# adc-digital.net
KiCad netlist of a schematic drawn in Altium Designer
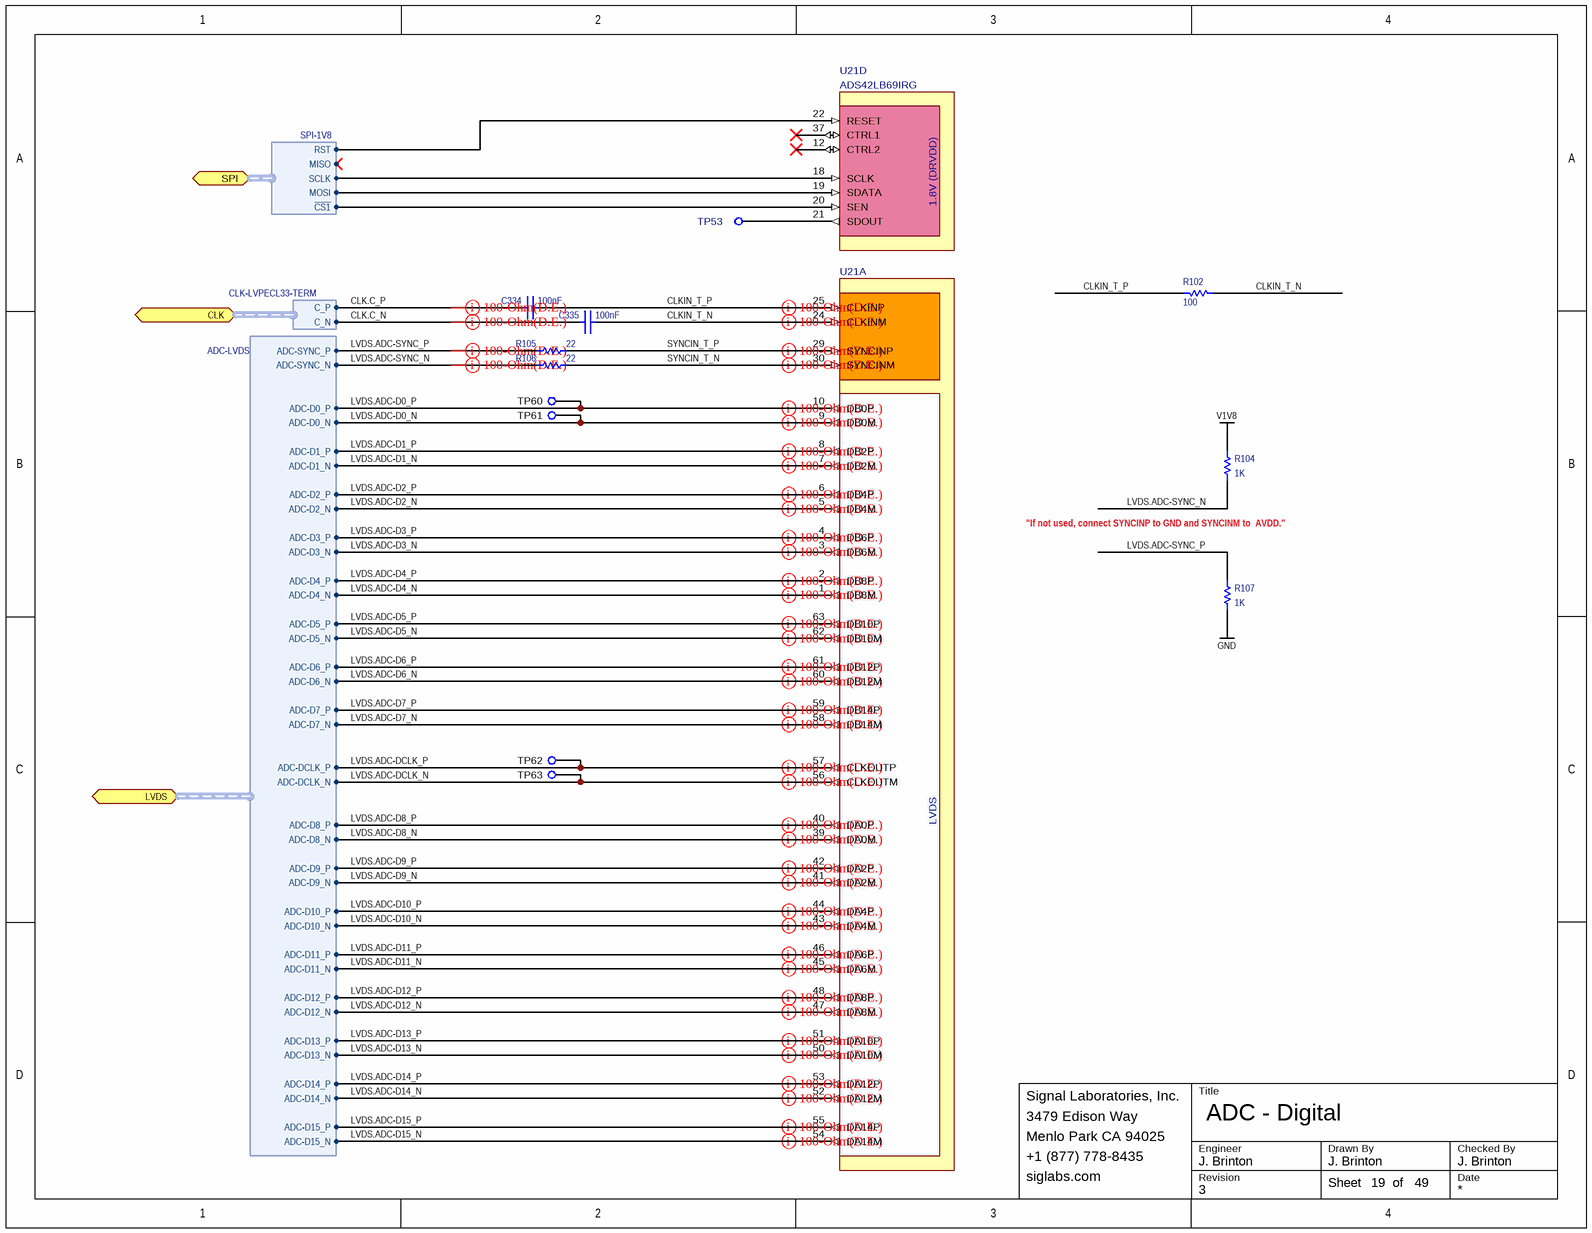
[diagram p0: adc-digital.SchDoc]

(export (version "E")
  (design (tool "Eeschema 10.0.6"))
  (components
    (comp (ref "C334")
      (value "100nF")
      (footprint "CAPC100X50X55L25N")
      (description "Ceramic Capacitor 100nF ±10% 16V X7R 0402")
      (fields (field (name "VOLTAGE") "16V") (field (name "MANUFACTURER") "Murata"))
      (libsource (lib "Graviton") (part "CAP 0402"))
    )
    (comp (ref "C335")
      (value "100nF")
      (footprint "CAPC100X50X55L25N")
      (description "Ceramic Capacitor 100nF ±10% 16V X7R 0402")
      (fields (field (name "VOLTAGE") "16V") (field (name "MANUFACTURER") "Murata"))
      (libsource (lib "Graviton") (part "CAP 0402"))
    )
    (comp (ref "R102")
      (value "100")
      (footprint "RESC1005X40N")
      (description "Thin Film Resistor 100 ±0.1% 0402")
      (fields (field (name "MANUFACTURER") "Panasonic") (field (name "TOLERANCE") "±0.1%"))
      (libsource (lib "Graviton") (part "RES 0402"))
    )
    (comp (ref "R104")
      (value "1K")
      (footprint "RESC1005X40N")
      (description "Thick Film Resistor 1k ±1% 0402")
      (fields (field (name "MANUFACTURER") "Yageo") (field (name "TOLERANCE") "±1%"))
      (libsource (lib "Graviton") (part "RES 0402"))
    )
    (comp (ref "R105")
      (value "22")
      (footprint "RESC1005X40N")
      (description "Thick Film Resistor 22 ±1% 0402")
      (fields (field (name "MANUFACTURER") "Yageo") (field (name "TOLERANCE") "±1%"))
      (libsource (lib "Graviton") (part "RES 0402"))
    )
    (comp (ref "R106")
      (value "22")
      (footprint "RESC1005X40N")
      (description "Thick Film Resistor 22 ±1% 0402")
      (fields (field (name "MANUFACTURER") "Yageo") (field (name "TOLERANCE") "±1%"))
      (libsource (lib "Graviton") (part "RES 0402"))
    )
    (comp (ref "R107")
      (value "1K")
      (footprint "RESC1005X40N")
      (description "Thick Film Resistor 1k ±1% 0402")
      (fields (field (name "MANUFACTURER") "Yageo") (field (name "TOLERANCE") "±1%"))
      (libsource (lib "Graviton") (part "RES 0402"))
    )
    (comp (ref "TP53")
      (value "TEST_POINT_SMD_50")
      (footprint "generic:TEST_POINT_SMD_10")
      (description "Test Point SMD")
      (libsource (lib "generic") (part "TEST_POINT_SMD_50"))
    )
    (comp (ref "TP60")
      (value "TEST_POINT_SMD_50")
      (footprint "generic:TEST_POINT_SMD_10")
      (description "Test Point SMD")
      (libsource (lib "generic") (part "TEST_POINT_SMD_50"))
    )
    (comp (ref "TP61")
      (value "TEST_POINT_SMD_50")
      (footprint "generic:TEST_POINT_SMD_10")
      (description "Test Point SMD")
      (libsource (lib "generic") (part "TEST_POINT_SMD_50"))
    )
    (comp (ref "TP62")
      (value "TEST_POINT_SMD_50")
      (footprint "generic:TEST_POINT_SMD_10")
      (description "Test Point SMD")
      (libsource (lib "generic") (part "TEST_POINT_SMD_50"))
    )
    (comp (ref "TP63")
      (value "TEST_POINT_SMD_50")
      (footprint "generic:TEST_POINT_SMD_10")
      (description "Test Point SMD")
      (libsource (lib "generic") (part "TEST_POINT_SMD_50"))
    )
    (comp (ref "U21")
      (value "ADS42LB69IRG")
      (footprint "S-PVQFN-N64")
      (description "Dual-Channel, 16-Bit, 250-MSPS Analog-to-Digital Converter")
      (fields (field (name "MANUFACTURER") "Texas Instruments"))
      (libsource (lib "ti") (part "ADS42LB69IRG"))
    )
  )
  (nets
    (net (code "4") (name "/CLK.C_N") (class "Default")
      (node (ref "C335") (pin "1") (pinfunction "1_1") (pintype "passive"))
    )
    (net (code "5") (name "/CLK.C_P") (class "Default")
      (node (ref "C334") (pin "1") (pinfunction "1_1") (pintype "passive"))
    )
    (net (code "6") (name "/CLKIN_T_N") (class "Default")
      (node (ref "C335") (pin "2") (pinfunction "2_2") (pintype "passive"))
      (node (ref "R102") (pin "2") (pinfunction "2_2") (pintype "passive"))
      (node (ref "U21") (pin "24") (pinfunction "CLKINM_24") (pintype "input"))
    )
    (net (code "7") (name "/CLKIN_T_P") (class "Default")
      (node (ref "C334") (pin "2") (pinfunction "2_2") (pintype "passive"))
      (node (ref "R102") (pin "1") (pinfunction "1_1") (pintype "passive"))
      (node (ref "U21") (pin "25") (pinfunction "CLKINP_25") (pintype "input"))
    )
    (net (code "8") (name "/LVDS.ADC-D0_N") (class "Default")
      (node (ref "TP61") (pin "1") (pinfunction "1_1") (pintype "passive"))
      (node (ref "U21") (pin "9") (pinfunction "DB0M_9") (pintype "output"))
    )
    (net (code "9") (name "/LVDS.ADC-D0_P") (class "Default")
      (node (ref "TP60") (pin "1") (pinfunction "1_1") (pintype "passive"))
      (node (ref "U21") (pin "10") (pinfunction "DB0P_10") (pintype "output"))
    )
    (net (code "10") (name "/LVDS.ADC-D1_N") (class "Default")
      (node (ref "U21") (pin "7") (pinfunction "DB2M_7") (pintype "output"))
    )
    (net (code "11") (name "/LVDS.ADC-D1_P") (class "Default")
      (node (ref "U21") (pin "8") (pinfunction "DB2P_8") (pintype "output"))
    )
    (net (code "12") (name "/LVDS.ADC-D2_N") (class "Default")
      (node (ref "U21") (pin "5") (pinfunction "DB4M_5") (pintype "output"))
    )
    (net (code "13") (name "/LVDS.ADC-D2_P") (class "Default")
      (node (ref "U21") (pin "6") (pinfunction "DB4P_6") (pintype "output"))
    )
    (net (code "14") (name "/LVDS.ADC-D3_N") (class "Default")
      (node (ref "U21") (pin "3") (pinfunction "DB6M_3") (pintype "output"))
    )
    (net (code "15") (name "/LVDS.ADC-D3_P") (class "Default")
      (node (ref "U21") (pin "4") (pinfunction "DB6P_4") (pintype "output"))
    )
    (net (code "16") (name "/LVDS.ADC-D4_N") (class "Default")
      (node (ref "U21") (pin "1") (pinfunction "DB8M_1") (pintype "output"))
    )
    (net (code "17") (name "/LVDS.ADC-D4_P") (class "Default")
      (node (ref "U21") (pin "2") (pinfunction "DB8P_2") (pintype "output"))
    )
    (net (code "18") (name "/LVDS.ADC-D5_N") (class "Default")
      (node (ref "U21") (pin "62") (pinfunction "DB10M_62") (pintype "output"))
    )
    (net (code "19") (name "/LVDS.ADC-D5_P") (class "Default")
      (node (ref "U21") (pin "63") (pinfunction "DB10P_63") (pintype "output"))
    )
    (net (code "20") (name "/LVDS.ADC-D6_N") (class "Default")
      (node (ref "U21") (pin "60") (pinfunction "DB12M_60") (pintype "output"))
    )
    (net (code "21") (name "/LVDS.ADC-D6_P") (class "Default")
      (node (ref "U21") (pin "61") (pinfunction "DB12P_61") (pintype "output"))
    )
    (net (code "22") (name "/LVDS.ADC-D7_N") (class "Default")
      (node (ref "U21") (pin "58") (pinfunction "DB14M_58") (pintype "output"))
    )
    (net (code "23") (name "/LVDS.ADC-D7_P") (class "Default")
      (node (ref "U21") (pin "59") (pinfunction "DB14P_59") (pintype "output"))
    )
    (net (code "24") (name "/LVDS.ADC-D8_N") (class "Default")
      (node (ref "U21") (pin "39") (pinfunction "DA0M_39") (pintype "output"))
    )
    (net (code "25") (name "/LVDS.ADC-D8_P") (class "Default")
      (node (ref "U21") (pin "40") (pinfunction "DA0P_40") (pintype "output"))
    )
    (net (code "26") (name "/LVDS.ADC-D9_N") (class "Default")
      (node (ref "U21") (pin "41") (pinfunction "DA2M_41") (pintype "output"))
    )
    (net (code "27") (name "/LVDS.ADC-D9_P") (class "Default")
      (node (ref "U21") (pin "42") (pinfunction "DA2P_42") (pintype "output"))
    )
    (net (code "28") (name "/LVDS.ADC-D10_N") (class "Default")
      (node (ref "U21") (pin "43") (pinfunction "DA4M_43") (pintype "output"))
    )
    (net (code "29") (name "/LVDS.ADC-D10_P") (class "Default")
      (node (ref "U21") (pin "44") (pinfunction "DA4P_44") (pintype "output"))
    )
    (net (code "30") (name "/LVDS.ADC-D11_N") (class "Default")
      (node (ref "U21") (pin "45") (pinfunction "DA6M_45") (pintype "output"))
    )
    (net (code "31") (name "/LVDS.ADC-D11_P") (class "Default")
      (node (ref "U21") (pin "46") (pinfunction "DA6P_46") (pintype "output"))
    )
    (net (code "32") (name "/LVDS.ADC-D12_N") (class "Default")
      (node (ref "U21") (pin "47") (pinfunction "DA8M_47") (pintype "output"))
    )
    (net (code "33") (name "/LVDS.ADC-D12_P") (class "Default")
      (node (ref "U21") (pin "48") (pinfunction "DA8P_48") (pintype "output"))
    )
    (net (code "34") (name "/LVDS.ADC-D13_N") (class "Default")
      (node (ref "U21") (pin "50") (pinfunction "DA10M_50") (pintype "output"))
    )
    (net (code "35") (name "/LVDS.ADC-D13_P") (class "Default")
      (node (ref "U21") (pin "51") (pinfunction "DA10P_51") (pintype "output"))
    )
    (net (code "36") (name "/LVDS.ADC-D14_N") (class "Default")
      (node (ref "U21") (pin "52") (pinfunction "DA12M_52") (pintype "output"))
    )
    (net (code "37") (name "/LVDS.ADC-D14_P") (class "Default")
      (node (ref "U21") (pin "53") (pinfunction "DA12P_53") (pintype "output"))
    )
    (net (code "38") (name "/LVDS.ADC-D15_N") (class "Default")
      (node (ref "U21") (pin "54") (pinfunction "DA14M_54") (pintype "output"))
    )
    (net (code "39") (name "/LVDS.ADC-D15_P") (class "Default")
      (node (ref "U21") (pin "55") (pinfunction "DA14P_55") (pintype "output"))
    )
    (net (code "40") (name "/LVDS.ADC-DCLK_N") (class "Default")
      (node (ref "TP63") (pin "1") (pinfunction "1_1") (pintype "passive"))
      (node (ref "U21") (pin "56") (pinfunction "CLKOUTM_56") (pintype "output"))
    )
    (net (code "41") (name "/LVDS.ADC-DCLK_P") (class "Default")
      (node (ref "TP62") (pin "1") (pinfunction "1_1") (pintype "passive"))
      (node (ref "U21") (pin "57") (pinfunction "CLKOUTP_57") (pintype "output"))
    )
    (net (code "42") (name "/LVDS.ADC-SYNC_N") (class "Default")
      (node (ref "R104") (pin "1") (pinfunction "1_1") (pintype "passive"))
      (node (ref "R106") (pin "1") (pinfunction "1_1") (pintype "passive"))
    )
    (net (code "43") (name "/LVDS.ADC-SYNC_P") (class "Default")
      (node (ref "R105") (pin "1") (pinfunction "1_1") (pintype "passive"))
      (node (ref "R107") (pin "2") (pinfunction "2_2") (pintype "passive"))
    )
    (net (code "44") (name "/MOSI") (class "Default")
      (node (ref "U21") (pin "19") (pinfunction "SDATA_19") (pintype "input"))
    )
    (net (code "45") (name "/RST") (class "Default")
      (node (ref "U21") (pin "22") (pinfunction "RESET_22") (pintype "input"))
    )
    (net (code "46") (name "/SCLK") (class "Default")
      (node (ref "U21") (pin "18") (pinfunction "SCLK_18") (pintype "input"))
    )
    (net (code "47") (name "/SYNCIN_T_N") (class "Default")
      (node (ref "R106") (pin "2") (pinfunction "2_2") (pintype "passive"))
      (node (ref "U21") (pin "30") (pinfunction "SYNCINM_30") (pintype "input"))
    )
    (net (code "48") (name "/SYNCIN_T_P") (class "Default")
      (node (ref "R105") (pin "2") (pinfunction "2_2") (pintype "passive"))
      (node (ref "U21") (pin "29") (pinfunction "SYNCINP_29") (pintype "input"))
    )
    (net (code "52") (name "/~{CS1}") (class "Default")
      (node (ref "U21") (pin "20") (pinfunction "SEN_20") (pintype "input"))
    )
    (net (code "53") (name "GND") (class "Default")
      (node (ref "R107") (pin "1") (pinfunction "1_1") (pintype "passive"))
    )
    (net (code "54") (name "Net-(U21D-SDOUT)") (class "Default")
      (node (ref "TP53") (pin "1") (pinfunction "1_1") (pintype "passive"))
      (node (ref "U21") (pin "21") (pinfunction "SDOUT_21") (pintype "output"))
    )
    (net (code "55") (name "V1V8") (class "Default")
      (node (ref "R104") (pin "2") (pinfunction "2_2") (pintype "passive"))
    )
    (net (code "56") (name "unconnected-(U21D-CTRL1-Pad37)") (class "Default")
      (node (ref "U21") (pin "37") (pinfunction "CTRL1_37") (pintype "bidirectional+no_connect"))
    )
    (net (code "57") (name "unconnected-(U21D-CTRL2-Pad12)") (class "Default")
      (node (ref "U21") (pin "12") (pinfunction "CTRL2_12") (pintype "bidirectional+no_connect"))
    )
  )
)
